# cloud-substrate.net
KiCad netlist of a schematic drawn in EAGLE
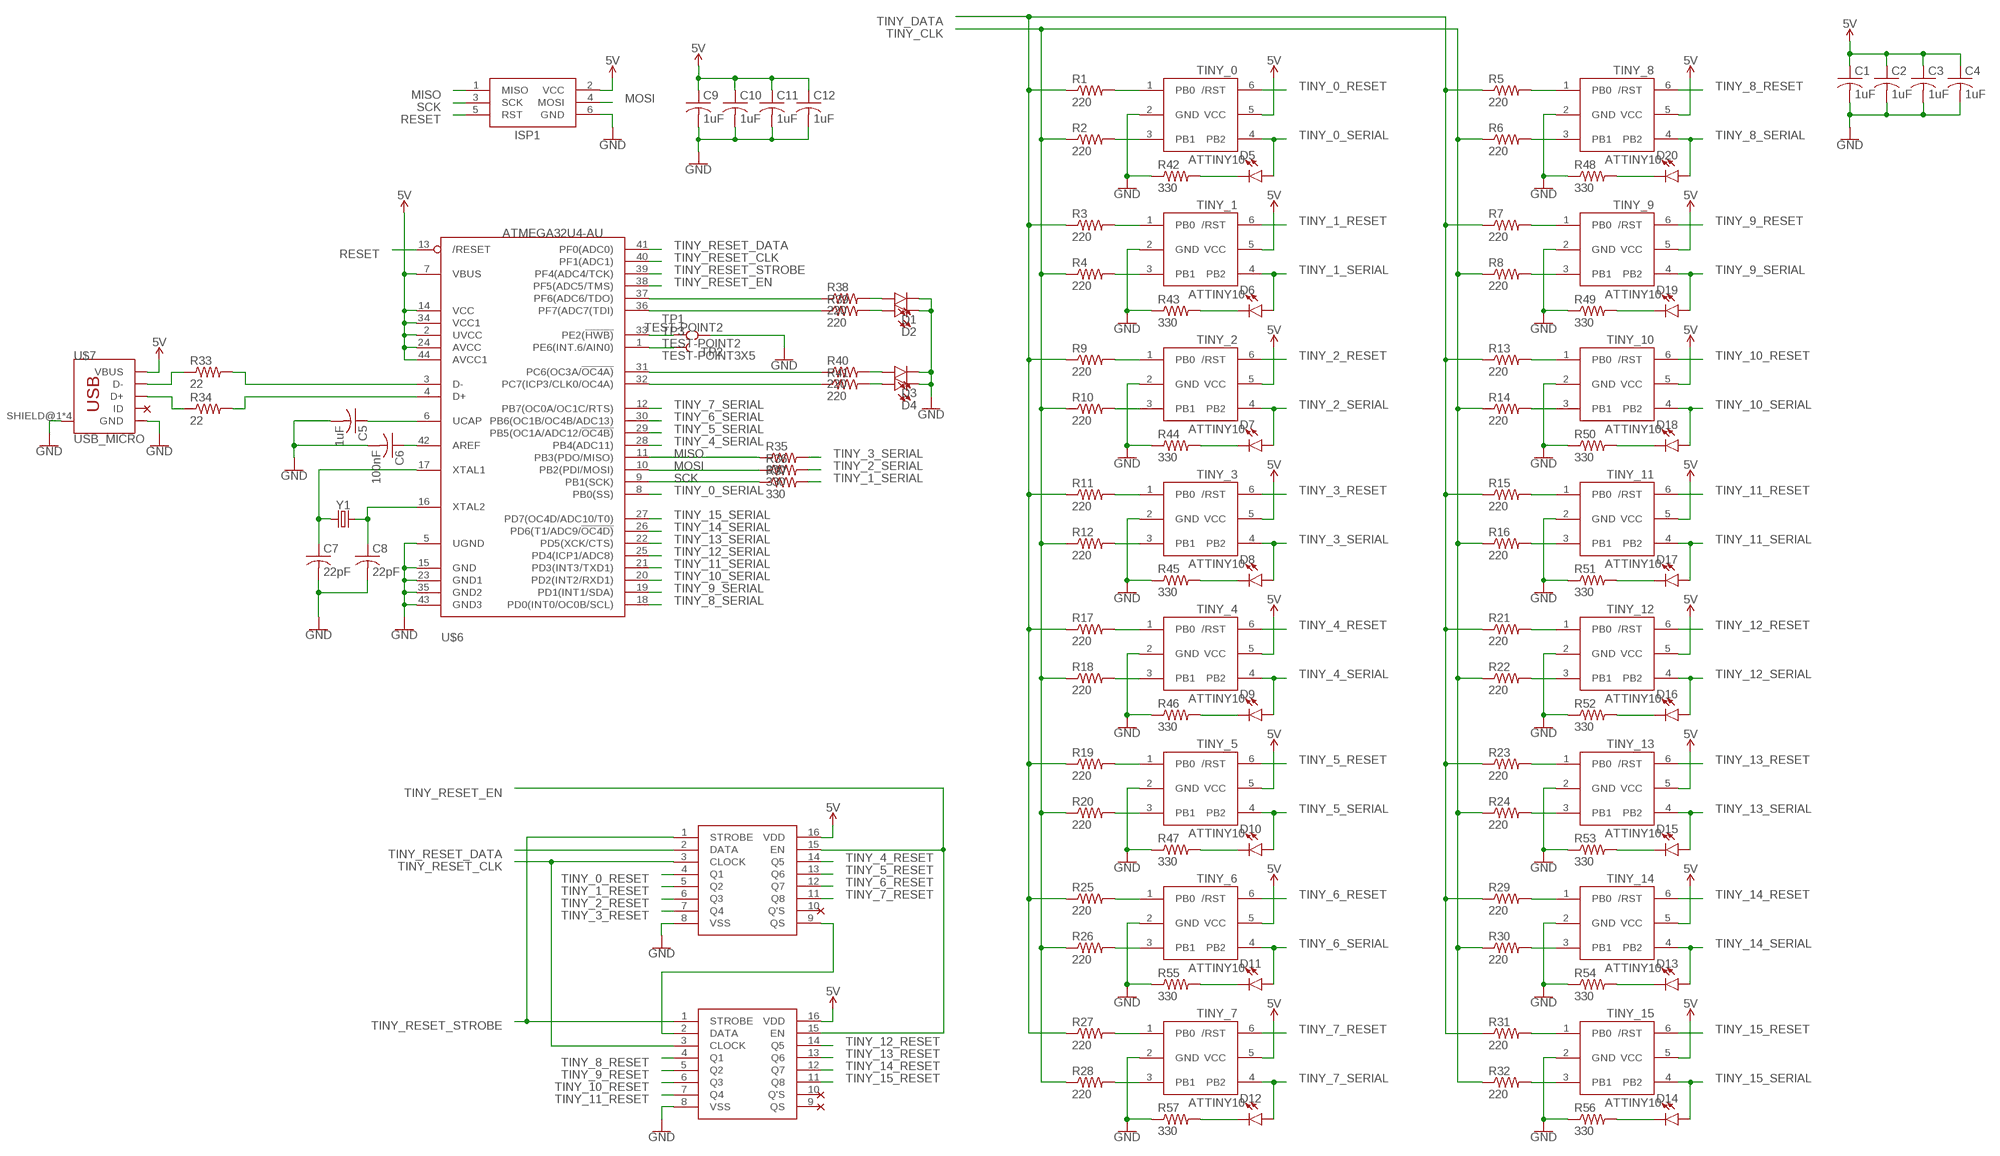
[diagram p0: schematic, sheet 1]

(export (version "E")
  (design (tool "Eeschema 10.0.6"))
  (components
    (comp (ref "C1")
      (value "1uF")
      (footprint "eagle-import:C0805")
      (libsource (lib "eagle-import") (part "C-USC0805"))
    )
    (comp (ref "C2")
      (value "1uF")
      (footprint "eagle-import:C0805")
      (libsource (lib "eagle-import") (part "C-USC0805"))
    )
    (comp (ref "C3")
      (value "1uF")
      (footprint "eagle-import:C0805")
      (libsource (lib "eagle-import") (part "C-USC0805"))
    )
    (comp (ref "C4")
      (value "1uF")
      (footprint "eagle-import:C0805")
      (libsource (lib "eagle-import") (part "C-USC0805"))
    )
    (comp (ref "C5")
      (value "1uF")
      (footprint "eagle-import:C0402")
      (libsource (lib "eagle-import") (part "C-USC0402"))
    )
    (comp (ref "C6")
      (value "100nF")
      (footprint "eagle-import:C0402")
      (libsource (lib "eagle-import") (part "C-USC0402"))
    )
    (comp (ref "C7")
      (value "22pF")
      (footprint "eagle-import:C0402")
      (libsource (lib "eagle-import") (part "C-USC0402"))
    )
    (comp (ref "C8")
      (value "22pF")
      (footprint "eagle-import:C0402")
      (libsource (lib "eagle-import") (part "C-USC0402"))
    )
    (comp (ref "C9")
      (value "1uF")
      (footprint "eagle-import:C0805")
      (libsource (lib "eagle-import") (part "C-USC0805"))
    )
    (comp (ref "C10")
      (value "1uF")
      (footprint "eagle-import:C0805")
      (libsource (lib "eagle-import") (part "C-USC0805"))
    )
    (comp (ref "C11")
      (value "1uF")
      (footprint "eagle-import:C0805")
      (libsource (lib "eagle-import") (part "C-USC0805"))
    )
    (comp (ref "C12")
      (value "1uF")
      (footprint "eagle-import:C0805")
      (libsource (lib "eagle-import") (part "C-USC0805"))
    )
    (comp (ref "D1")
      (value "LED0603")
      (footprint "eagle-import:LED-0603")
      (libsource (lib "eagle-import") (part "LED0603"))
    )
    (comp (ref "D2")
      (value "LED0603")
      (footprint "eagle-import:LED-0603")
      (libsource (lib "eagle-import") (part "LED0603"))
    )
    (comp (ref "D3")
      (value "LED0603")
      (footprint "eagle-import:LED-0603")
      (libsource (lib "eagle-import") (part "LED0603"))
    )
    (comp (ref "D4")
      (value "LED0603")
      (footprint "eagle-import:LED-0603")
      (libsource (lib "eagle-import") (part "LED0603"))
    )
    (comp (ref "D5")
      (value "LED0603")
      (footprint "eagle-import:LED-0603")
      (libsource (lib "eagle-import") (part "LED0603"))
    )
    (comp (ref "D6")
      (value "LED0603")
      (footprint "eagle-import:LED-0603")
      (libsource (lib "eagle-import") (part "LED0603"))
    )
    (comp (ref "D7")
      (value "LED0603")
      (footprint "eagle-import:LED-0603")
      (libsource (lib "eagle-import") (part "LED0603"))
    )
    (comp (ref "D8")
      (value "LED0603")
      (footprint "eagle-import:LED-0603")
      (libsource (lib "eagle-import") (part "LED0603"))
    )
    (comp (ref "D9")
      (value "LED0603")
      (footprint "eagle-import:LED-0603")
      (libsource (lib "eagle-import") (part "LED0603"))
    )
    (comp (ref "D10")
      (value "LED0603")
      (footprint "eagle-import:LED-0603")
      (libsource (lib "eagle-import") (part "LED0603"))
    )
    (comp (ref "D11")
      (value "LED0603")
      (footprint "eagle-import:LED-0603")
      (libsource (lib "eagle-import") (part "LED0603"))
    )
    (comp (ref "D12")
      (value "LED0603")
      (footprint "eagle-import:LED-0603")
      (libsource (lib "eagle-import") (part "LED0603"))
    )
    (comp (ref "D13")
      (value "LED0603")
      (footprint "eagle-import:LED-0603")
      (libsource (lib "eagle-import") (part "LED0603"))
    )
    (comp (ref "D14")
      (value "LED0603")
      (footprint "eagle-import:LED-0603")
      (libsource (lib "eagle-import") (part "LED0603"))
    )
    (comp (ref "D15")
      (value "LED0603")
      (footprint "eagle-import:LED-0603")
      (libsource (lib "eagle-import") (part "LED0603"))
    )
    (comp (ref "D16")
      (value "LED0603")
      (footprint "eagle-import:LED-0603")
      (libsource (lib "eagle-import") (part "LED0603"))
    )
    (comp (ref "D17")
      (value "LED0603")
      (footprint "eagle-import:LED-0603")
      (libsource (lib "eagle-import") (part "LED0603"))
    )
    (comp (ref "D18")
      (value "LED0603")
      (footprint "eagle-import:LED-0603")
      (libsource (lib "eagle-import") (part "LED0603"))
    )
    (comp (ref "D19")
      (value "LED0603")
      (footprint "eagle-import:LED-0603")
      (libsource (lib "eagle-import") (part "LED0603"))
    )
    (comp (ref "D20")
      (value "LED0603")
      (footprint "eagle-import:LED-0603")
      (libsource (lib "eagle-import") (part "LED0603"))
    )
    (comp (ref "ISP1")
      (value "AVRISP-6")
      (footprint "eagle-import:AVRISP")
      (libsource (lib "eagle-import") (part "AVRISP-6"))
    )
    (comp (ref "R1")
      (value "220")
      (footprint "eagle-import:R0402")
      (libsource (lib "eagle-import") (part "R-US_R0402"))
    )
    (comp (ref "R2")
      (value "220")
      (footprint "eagle-import:R0402")
      (libsource (lib "eagle-import") (part "R-US_R0402"))
    )
    (comp (ref "R3")
      (value "220")
      (footprint "eagle-import:R0402")
      (libsource (lib "eagle-import") (part "R-US_R0402"))
    )
    (comp (ref "R4")
      (value "220")
      (footprint "eagle-import:R0402")
      (libsource (lib "eagle-import") (part "R-US_R0402"))
    )
    (comp (ref "R5")
      (value "220")
      (footprint "eagle-import:R0402")
      (libsource (lib "eagle-import") (part "R-US_R0402"))
    )
    (comp (ref "R6")
      (value "220")
      (footprint "eagle-import:R0402")
      (libsource (lib "eagle-import") (part "R-US_R0402"))
    )
    (comp (ref "R7")
      (value "220")
      (footprint "eagle-import:R0402")
      (libsource (lib "eagle-import") (part "R-US_R0402"))
    )
    (comp (ref "R8")
      (value "220")
      (footprint "eagle-import:R0402")
      (libsource (lib "eagle-import") (part "R-US_R0402"))
    )
    (comp (ref "R9")
      (value "220")
      (footprint "eagle-import:R0402")
      (libsource (lib "eagle-import") (part "R-US_R0402"))
    )
    (comp (ref "R10")
      (value "220")
      (footprint "eagle-import:R0402")
      (libsource (lib "eagle-import") (part "R-US_R0402"))
    )
    (comp (ref "R11")
      (value "220")
      (footprint "eagle-import:R0402")
      (libsource (lib "eagle-import") (part "R-US_R0402"))
    )
    (comp (ref "R12")
      (value "220")
      (footprint "eagle-import:R0402")
      (libsource (lib "eagle-import") (part "R-US_R0402"))
    )
    (comp (ref "R13")
      (value "220")
      (footprint "eagle-import:R0402")
      (libsource (lib "eagle-import") (part "R-US_R0402"))
    )
    (comp (ref "R14")
      (value "220")
      (footprint "eagle-import:R0402")
      (libsource (lib "eagle-import") (part "R-US_R0402"))
    )
    (comp (ref "R15")
      (value "220")
      (footprint "eagle-import:R0402")
      (libsource (lib "eagle-import") (part "R-US_R0402"))
    )
    (comp (ref "R16")
      (value "220")
      (footprint "eagle-import:R0402")
      (libsource (lib "eagle-import") (part "R-US_R0402"))
    )
    (comp (ref "R17")
      (value "220")
      (footprint "eagle-import:R0402")
      (libsource (lib "eagle-import") (part "R-US_R0402"))
    )
    (comp (ref "R18")
      (value "220")
      (footprint "eagle-import:R0402")
      (libsource (lib "eagle-import") (part "R-US_R0402"))
    )
    (comp (ref "R19")
      (value "220")
      (footprint "eagle-import:R0402")
      (libsource (lib "eagle-import") (part "R-US_R0402"))
    )
    (comp (ref "R20")
      (value "220")
      (footprint "eagle-import:R0402")
      (libsource (lib "eagle-import") (part "R-US_R0402"))
    )
    (comp (ref "R21")
      (value "220")
      (footprint "eagle-import:R0402")
      (libsource (lib "eagle-import") (part "R-US_R0402"))
    )
    (comp (ref "R22")
      (value "220")
      (footprint "eagle-import:R0402")
      (libsource (lib "eagle-import") (part "R-US_R0402"))
    )
    (comp (ref "R23")
      (value "220")
      (footprint "eagle-import:R0402")
      (libsource (lib "eagle-import") (part "R-US_R0402"))
    )
    (comp (ref "R24")
      (value "220")
      (footprint "eagle-import:R0402")
      (libsource (lib "eagle-import") (part "R-US_R0402"))
    )
    (comp (ref "R25")
      (value "220")
      (footprint "eagle-import:R0402")
      (libsource (lib "eagle-import") (part "R-US_R0402"))
    )
    (comp (ref "R26")
      (value "220")
      (footprint "eagle-import:R0402")
      (libsource (lib "eagle-import") (part "R-US_R0402"))
    )
    (comp (ref "R27")
      (value "220")
      (footprint "eagle-import:R0402")
      (libsource (lib "eagle-import") (part "R-US_R0402"))
    )
    (comp (ref "R28")
      (value "220")
      (footprint "eagle-import:R0402")
      (libsource (lib "eagle-import") (part "R-US_R0402"))
    )
    (comp (ref "R29")
      (value "220")
      (footprint "eagle-import:R0402")
      (libsource (lib "eagle-import") (part "R-US_R0402"))
    )
    (comp (ref "R30")
      (value "220")
      (footprint "eagle-import:R0402")
      (libsource (lib "eagle-import") (part "R-US_R0402"))
    )
    (comp (ref "R31")
      (value "220")
      (footprint "eagle-import:R0402")
      (libsource (lib "eagle-import") (part "R-US_R0402"))
    )
    (comp (ref "R32")
      (value "220")
      (footprint "eagle-import:R0402")
      (libsource (lib "eagle-import") (part "R-US_R0402"))
    )
    (comp (ref "R33")
      (value "22")
      (footprint "eagle-import:R0402")
      (libsource (lib "eagle-import") (part "R-US_R0402"))
    )
    (comp (ref "R34")
      (value "22")
      (footprint "eagle-import:R0402")
      (libsource (lib "eagle-import") (part "R-US_R0402"))
    )
    (comp (ref "R35")
      (value "330")
      (footprint "eagle-import:R0402")
      (libsource (lib "eagle-import") (part "R-US_R0402"))
    )
    (comp (ref "R36")
      (value "330")
      (footprint "eagle-import:R0402")
      (libsource (lib "eagle-import") (part "R-US_R0402"))
    )
    (comp (ref "R37")
      (value "330")
      (footprint "eagle-import:R0402")
      (libsource (lib "eagle-import") (part "R-US_R0402"))
    )
    (comp (ref "R38")
      (value "220")
      (footprint "eagle-import:R0402")
      (libsource (lib "eagle-import") (part "R-US_R0402"))
    )
    (comp (ref "R39")
      (value "220")
      (footprint "eagle-import:R0402")
      (libsource (lib "eagle-import") (part "R-US_R0402"))
    )
    (comp (ref "R40")
      (value "220")
      (footprint "eagle-import:R0402")
      (libsource (lib "eagle-import") (part "R-US_R0402"))
    )
    (comp (ref "R41")
      (value "220")
      (footprint "eagle-import:R0402")
      (libsource (lib "eagle-import") (part "R-US_R0402"))
    )
    (comp (ref "R42")
      (value "330")
      (footprint "eagle-import:R0402")
      (libsource (lib "eagle-import") (part "R-US_R0402"))
    )
    (comp (ref "R43")
      (value "330")
      (footprint "eagle-import:R0402")
      (libsource (lib "eagle-import") (part "R-US_R0402"))
    )
    (comp (ref "R44")
      (value "330")
      (footprint "eagle-import:R0402")
      (libsource (lib "eagle-import") (part "R-US_R0402"))
    )
    (comp (ref "R45")
      (value "330")
      (footprint "eagle-import:R0402")
      (libsource (lib "eagle-import") (part "R-US_R0402"))
    )
    (comp (ref "R46")
      (value "330")
      (footprint "eagle-import:R0402")
      (libsource (lib "eagle-import") (part "R-US_R0402"))
    )
    (comp (ref "R47")
      (value "330")
      (footprint "eagle-import:R0402")
      (libsource (lib "eagle-import") (part "R-US_R0402"))
    )
    (comp (ref "R48")
      (value "330")
      (footprint "eagle-import:R0402")
      (libsource (lib "eagle-import") (part "R-US_R0402"))
    )
    (comp (ref "R49")
      (value "330")
      (footprint "eagle-import:R0402")
      (libsource (lib "eagle-import") (part "R-US_R0402"))
    )
    (comp (ref "R50")
      (value "330")
      (footprint "eagle-import:R0402")
      (libsource (lib "eagle-import") (part "R-US_R0402"))
    )
    (comp (ref "R51")
      (value "330")
      (footprint "eagle-import:R0402")
      (libsource (lib "eagle-import") (part "R-US_R0402"))
    )
    (comp (ref "R52")
      (value "330")
      (footprint "eagle-import:R0402")
      (libsource (lib "eagle-import") (part "R-US_R0402"))
    )
    (comp (ref "R53")
      (value "330")
      (footprint "eagle-import:R0402")
      (libsource (lib "eagle-import") (part "R-US_R0402"))
    )
    (comp (ref "R54")
      (value "330")
      (footprint "eagle-import:R0402")
      (libsource (lib "eagle-import") (part "R-US_R0402"))
    )
    (comp (ref "R55")
      (value "330")
      (footprint "eagle-import:R0402")
      (libsource (lib "eagle-import") (part "R-US_R0402"))
    )
    (comp (ref "R56")
      (value "330")
      (footprint "eagle-import:R0402")
      (libsource (lib "eagle-import") (part "R-US_R0402"))
    )
    (comp (ref "R57")
      (value "330")
      (footprint "eagle-import:R0402")
      (libsource (lib "eagle-import") (part "R-US_R0402"))
    )
    (comp (ref "TINY_0")
      (value "ATTINY10")
      (footprint "eagle-import:SOT23-6")
      (libsource (lib "eagle-import") (part "ATTINY10"))
    )
    (comp (ref "TINY_1")
      (value "ATTINY10")
      (footprint "eagle-import:SOT23-6")
      (libsource (lib "eagle-import") (part "ATTINY10"))
    )
    (comp (ref "TINY_2")
      (value "ATTINY10")
      (footprint "eagle-import:SOT23-6")
      (libsource (lib "eagle-import") (part "ATTINY10"))
    )
    (comp (ref "TINY_3")
      (value "ATTINY10")
      (footprint "eagle-import:SOT23-6")
      (libsource (lib "eagle-import") (part "ATTINY10"))
    )
    (comp (ref "TINY_4")
      (value "ATTINY10")
      (footprint "eagle-import:SOT23-6")
      (libsource (lib "eagle-import") (part "ATTINY10"))
    )
    (comp (ref "TINY_5")
      (value "ATTINY10")
      (footprint "eagle-import:SOT23-6")
      (libsource (lib "eagle-import") (part "ATTINY10"))
    )
    (comp (ref "TINY_6")
      (value "ATTINY10")
      (footprint "eagle-import:SOT23-6")
      (libsource (lib "eagle-import") (part "ATTINY10"))
    )
    (comp (ref "TINY_7")
      (value "ATTINY10")
      (footprint "eagle-import:SOT23-6")
      (libsource (lib "eagle-import") (part "ATTINY10"))
    )
    (comp (ref "TINY_8")
      (value "ATTINY10")
      (footprint "eagle-import:SOT23-6")
      (libsource (lib "eagle-import") (part "ATTINY10"))
    )
    (comp (ref "TINY_9")
      (value "ATTINY10")
      (footprint "eagle-import:SOT23-6")
      (libsource (lib "eagle-import") (part "ATTINY10"))
    )
    (comp (ref "TINY_10")
      (value "ATTINY10")
      (footprint "eagle-import:SOT23-6")
      (libsource (lib "eagle-import") (part "ATTINY10"))
    )
    (comp (ref "TINY_11")
      (value "ATTINY10")
      (footprint "eagle-import:SOT23-6")
      (libsource (lib "eagle-import") (part "ATTINY10"))
    )
    (comp (ref "TINY_12")
      (value "ATTINY10")
      (footprint "eagle-import:SOT23-6")
      (libsource (lib "eagle-import") (part "ATTINY10"))
    )
    (comp (ref "TINY_13")
      (value "ATTINY10")
      (footprint "eagle-import:SOT23-6")
      (libsource (lib "eagle-import") (part "ATTINY10"))
    )
    (comp (ref "TINY_14")
      (value "ATTINY10")
      (footprint "eagle-import:SOT23-6")
      (libsource (lib "eagle-import") (part "ATTINY10"))
    )
    (comp (ref "TINY_15")
      (value "ATTINY10")
      (footprint "eagle-import:SOT23-6")
      (libsource (lib "eagle-import") (part "ATTINY10"))
    )
    (comp (ref "TP1")
      (value "TEST-POINT2")
      (footprint "eagle-import:PAD.02X.02")
      (libsource (lib "eagle-import") (part "TEST-POINT2"))
    )
    (comp (ref "TP2")
      (value "TEST-POINT2")
      (footprint "eagle-import:PAD.02X.02")
      (libsource (lib "eagle-import") (part "TEST-POINT2"))
    )
    (comp (ref "TP3")
      (value "TEST-POINT3X5")
      (footprint "eagle-import:PAD.03X.05")
      (libsource (lib "eagle-import") (part "TEST-POINT3X5"))
    )
    (comp (ref "U$1")
      (value "CD4094B")
      (footprint "eagle-import:TSSOP16")
      (libsource (lib "eagle-import") (part "CD4094B"))
    )
    (comp (ref "U$2")
      (value "CD4094B")
      (footprint "eagle-import:TSSOP16")
      (libsource (lib "eagle-import") (part "CD4094B"))
    )
    (comp (ref "U$6")
      (value "ATMEGA32U4-AU")
      (footprint "eagle-import:TQFP44")
      (libsource (lib "eagle-import") (part "ATMEGA32U4-AU"))
    )
    (comp (ref "U$7")
      (value "USB_MICRO")
      (footprint "eagle-import:USB_FCI_10118194")
      (libsource (lib "eagle-import") (part "USB_MICRO"))
    )
    (comp (ref "Y1")
      (value "CRYSTALSMD-3.2X2.5")
      (footprint "eagle-import:CRYSTAL-SMD-3.2X2.5MM")
      (libsource (lib "eagle-import") (part "CRYSTALSMD-3.2X2.5"))
    )
  )
  (nets
    (net (code "1") (name "/MISO") (class "Default")
      (node (ref "ISP1") (pin "1") (pinfunction "MISO_1") (pintype "input"))
      (node (ref "R35") (pin "1") (pinfunction "1_1") (pintype "passive"))
      (node (ref "U$6") (pin "11") (pinfunction "PB3(PDO/MISO)_11") (pintype "bidirectional"))
    )
    (net (code "2") (name "/MOSI") (class "Default")
      (node (ref "ISP1") (pin "4") (pinfunction "MOSI_4") (pintype "output"))
      (node (ref "R36") (pin "1") (pinfunction "1_1") (pintype "passive"))
      (node (ref "U$6") (pin "10") (pinfunction "PB2(PDI/MOSI)_10") (pintype "bidirectional"))
    )
    (net (code "3") (name "/RESET") (class "Default")
      (node (ref "ISP1") (pin "5") (pinfunction "RST_5") (pintype "output"))
      (node (ref "U$6") (pin "13") (pinfunction "/RESET_13") (pintype "bidirectional"))
    )
    (net (code "4") (name "/SCK") (class "Default")
      (node (ref "ISP1") (pin "3") (pinfunction "SCK_3") (pintype "output"))
      (node (ref "R37") (pin "1") (pinfunction "1_1") (pintype "passive"))
      (node (ref "U$6") (pin "9") (pinfunction "PB1(SCK)_9") (pintype "bidirectional"))
    )
    (net (code "5") (name "/TINY_0_RESET") (class "Default")
      (node (ref "TINY_0") (pin "6") (pinfunction "/RST_6") (pintype "bidirectional"))
      (node (ref "U$1") (pin "4") (pinfunction "Q1_4") (pintype "bidirectional"))
    )
    (net (code "6") (name "/TINY_0_SERIAL") (class "Default")
      (node (ref "D5") (pin "A") (pinfunction "A_A") (pintype "passive"))
      (node (ref "TINY_0") (pin "4") (pinfunction "PB2_4") (pintype "bidirectional"))
      (node (ref "U$6") (pin "8") (pinfunction "PB0(SS)_8") (pintype "bidirectional"))
    )
    (net (code "7") (name "/TINY_1_RESET") (class "Default")
      (node (ref "TINY_1") (pin "6") (pinfunction "/RST_6") (pintype "bidirectional"))
      (node (ref "U$1") (pin "5") (pinfunction "Q2_5") (pintype "bidirectional"))
    )
    (net (code "8") (name "/TINY_1_SERIAL") (class "Default")
      (node (ref "D6") (pin "A") (pinfunction "A_A") (pintype "passive"))
      (node (ref "R37") (pin "2") (pinfunction "2_2") (pintype "passive"))
      (node (ref "TINY_1") (pin "4") (pinfunction "PB2_4") (pintype "bidirectional"))
    )
    (net (code "9") (name "/TINY_2_RESET") (class "Default")
      (node (ref "TINY_2") (pin "6") (pinfunction "/RST_6") (pintype "bidirectional"))
      (node (ref "U$1") (pin "6") (pinfunction "Q3_6") (pintype "bidirectional"))
    )
    (net (code "10") (name "/TINY_2_SERIAL") (class "Default")
      (node (ref "D7") (pin "A") (pinfunction "A_A") (pintype "passive"))
      (node (ref "R36") (pin "2") (pinfunction "2_2") (pintype "passive"))
      (node (ref "TINY_2") (pin "4") (pinfunction "PB2_4") (pintype "bidirectional"))
    )
    (net (code "11") (name "/TINY_3_RESET") (class "Default")
      (node (ref "TINY_3") (pin "6") (pinfunction "/RST_6") (pintype "bidirectional"))
      (node (ref "U$1") (pin "7") (pinfunction "Q4_7") (pintype "bidirectional"))
    )
    (net (code "12") (name "/TINY_3_SERIAL") (class "Default")
      (node (ref "D8") (pin "A") (pinfunction "A_A") (pintype "passive"))
      (node (ref "R35") (pin "2") (pinfunction "2_2") (pintype "passive"))
      (node (ref "TINY_3") (pin "4") (pinfunction "PB2_4") (pintype "bidirectional"))
    )
    (net (code "13") (name "/TINY_4_RESET") (class "Default")
      (node (ref "TINY_4") (pin "6") (pinfunction "/RST_6") (pintype "bidirectional"))
      (node (ref "U$1") (pin "14") (pinfunction "Q5_14") (pintype "bidirectional"))
    )
    (net (code "14") (name "/TINY_4_SERIAL") (class "Default")
      (node (ref "D9") (pin "A") (pinfunction "A_A") (pintype "passive"))
      (node (ref "TINY_4") (pin "4") (pinfunction "PB2_4") (pintype "bidirectional"))
      (node (ref "U$6") (pin "28") (pinfunction "PB4(ADC11)_28") (pintype "bidirectional"))
    )
    (net (code "15") (name "/TINY_5_RESET") (class "Default")
      (node (ref "TINY_5") (pin "6") (pinfunction "/RST_6") (pintype "bidirectional"))
      (node (ref "U$1") (pin "13") (pinfunction "Q6_13") (pintype "bidirectional"))
    )
    (net (code "16") (name "/TINY_5_SERIAL") (class "Default")
      (node (ref "D10") (pin "A") (pinfunction "A_A") (pintype "passive"))
      (node (ref "TINY_5") (pin "4") (pinfunction "PB2_4") (pintype "bidirectional"))
      (node (ref "U$6") (pin "29") (pinfunction "PB5(OC1A/ADC12/~{OC4B})_29") (pintype "bidirectional"))
    )
    (net (code "17") (name "/TINY_6_RESET") (class "Default")
      (node (ref "TINY_6") (pin "6") (pinfunction "/RST_6") (pintype "bidirectional"))
      (node (ref "U$1") (pin "12") (pinfunction "Q7_12") (pintype "bidirectional"))
    )
    (net (code "18") (name "/TINY_6_SERIAL") (class "Default")
      (node (ref "D11") (pin "A") (pinfunction "A_A") (pintype "passive"))
      (node (ref "TINY_6") (pin "4") (pinfunction "PB2_4") (pintype "bidirectional"))
      (node (ref "U$6") (pin "30") (pinfunction "PB6(OC1B/OC4B/ADC13)_30") (pintype "bidirectional"))
    )
    (net (code "19") (name "/TINY_7_RESET") (class "Default")
      (node (ref "TINY_7") (pin "6") (pinfunction "/RST_6") (pintype "bidirectional"))
      (node (ref "U$1") (pin "11") (pinfunction "Q8_11") (pintype "bidirectional"))
    )
    (net (code "20") (name "/TINY_7_SERIAL") (class "Default")
      (node (ref "D12") (pin "A") (pinfunction "A_A") (pintype "passive"))
      (node (ref "TINY_7") (pin "4") (pinfunction "PB2_4") (pintype "bidirectional"))
      (node (ref "U$6") (pin "12") (pinfunction "PB7(OC0A/OC1C/RTS)_12") (pintype "bidirectional"))
    )
    (net (code "21") (name "/TINY_8_RESET") (class "Default")
      (node (ref "TINY_8") (pin "6") (pinfunction "/RST_6") (pintype "bidirectional"))
      (node (ref "U$2") (pin "4") (pinfunction "Q1_4") (pintype "bidirectional"))
    )
    (net (code "22") (name "/TINY_8_SERIAL") (class "Default")
      (node (ref "D20") (pin "A") (pinfunction "A_A") (pintype "passive"))
      (node (ref "TINY_8") (pin "4") (pinfunction "PB2_4") (pintype "bidirectional"))
      (node (ref "U$6") (pin "18") (pinfunction "PD0(INT0/OC0B/SCL)_18") (pintype "bidirectional"))
    )
    (net (code "23") (name "/TINY_9_RESET") (class "Default")
      (node (ref "TINY_9") (pin "6") (pinfunction "/RST_6") (pintype "bidirectional"))
      (node (ref "U$2") (pin "5") (pinfunction "Q2_5") (pintype "bidirectional"))
    )
    (net (code "24") (name "/TINY_9_SERIAL") (class "Default")
      (node (ref "D19") (pin "A") (pinfunction "A_A") (pintype "passive"))
      (node (ref "TINY_9") (pin "4") (pinfunction "PB2_4") (pintype "bidirectional"))
      (node (ref "U$6") (pin "19") (pinfunction "PD1(INT1/SDA)_19") (pintype "bidirectional"))
    )
    (net (code "25") (name "/TINY_10_RESET") (class "Default")
      (node (ref "TINY_10") (pin "6") (pinfunction "/RST_6") (pintype "bidirectional"))
      (node (ref "U$2") (pin "6") (pinfunction "Q3_6") (pintype "bidirectional"))
    )
    (net (code "26") (name "/TINY_10_SERIAL") (class "Default")
      (node (ref "D18") (pin "A") (pinfunction "A_A") (pintype "passive"))
      (node (ref "TINY_10") (pin "4") (pinfunction "PB2_4") (pintype "bidirectional"))
      (node (ref "U$6") (pin "20") (pinfunction "PD2(INT2/RXD1)_20") (pintype "bidirectional"))
    )
    (net (code "27") (name "/TINY_11_RESET") (class "Default")
      (node (ref "TINY_11") (pin "6") (pinfunction "/RST_6") (pintype "bidirectional"))
      (node (ref "U$2") (pin "7") (pinfunction "Q4_7") (pintype "bidirectional"))
    )
    (net (code "28") (name "/TINY_11_SERIAL") (class "Default")
      (node (ref "D17") (pin "A") (pinfunction "A_A") (pintype "passive"))
      (node (ref "TINY_11") (pin "4") (pinfunction "PB2_4") (pintype "bidirectional"))
      (node (ref "U$6") (pin "21") (pinfunction "PD3(INT3/TXD1)_21") (pintype "bidirectional"))
    )
    (net (code "29") (name "/TINY_12_RESET") (class "Default")
      (node (ref "TINY_12") (pin "6") (pinfunction "/RST_6") (pintype "bidirectional"))
      (node (ref "U$2") (pin "14") (pinfunction "Q5_14") (pintype "bidirectional"))
    )
    (net (code "30") (name "/TINY_12_SERIAL") (class "Default")
      (node (ref "D16") (pin "A") (pinfunction "A_A") (pintype "passive"))
      (node (ref "TINY_12") (pin "4") (pinfunction "PB2_4") (pintype "bidirectional"))
      (node (ref "U$6") (pin "25") (pinfunction "PD4(ICP1/ADC8)_25") (pintype "bidirectional"))
    )
    (net (code "31") (name "/TINY_13_RESET") (class "Default")
      (node (ref "TINY_13") (pin "6") (pinfunction "/RST_6") (pintype "bidirectional"))
      (node (ref "U$2") (pin "13") (pinfunction "Q6_13") (pintype "bidirectional"))
    )
    (net (code "32") (name "/TINY_13_SERIAL") (class "Default")
      (node (ref "D15") (pin "A") (pinfunction "A_A") (pintype "passive"))
      (node (ref "TINY_13") (pin "4") (pinfunction "PB2_4") (pintype "bidirectional"))
      (node (ref "U$6") (pin "22") (pinfunction "PD5(XCK/CTS)_22") (pintype "bidirectional"))
    )
    (net (code "33") (name "/TINY_14_RESET") (class "Default")
      (node (ref "TINY_14") (pin "6") (pinfunction "/RST_6") (pintype "bidirectional"))
      (node (ref "U$2") (pin "12") (pinfunction "Q7_12") (pintype "bidirectional"))
    )
    (net (code "34") (name "/TINY_14_SERIAL") (class "Default")
      (node (ref "D13") (pin "A") (pinfunction "A_A") (pintype "passive"))
      (node (ref "TINY_14") (pin "4") (pinfunction "PB2_4") (pintype "bidirectional"))
      (node (ref "U$6") (pin "26") (pinfunction "PD6(T1/ADC9/~{OC4D})_26") (pintype "bidirectional"))
    )
    (net (code "35") (name "/TINY_15_RESET") (class "Default")
      (node (ref "TINY_15") (pin "6") (pinfunction "/RST_6") (pintype "bidirectional"))
      (node (ref "U$2") (pin "11") (pinfunction "Q8_11") (pintype "bidirectional"))
    )
    (net (code "36") (name "/TINY_15_SERIAL") (class "Default")
      (node (ref "D14") (pin "A") (pinfunction "A_A") (pintype "passive"))
      (node (ref "TINY_15") (pin "4") (pinfunction "PB2_4") (pintype "bidirectional"))
      (node (ref "U$6") (pin "27") (pinfunction "PD7(OC4D/ADC10/T0)_27") (pintype "bidirectional"))
    )
    (net (code "37") (name "/TINY_CLK") (class "Default")
      (node (ref "R10") (pin "1") (pinfunction "1_1") (pintype "passive"))
      (node (ref "R12") (pin "1") (pinfunction "1_1") (pintype "passive"))
      (node (ref "R14") (pin "1") (pinfunction "1_1") (pintype "passive"))
      (node (ref "R16") (pin "1") (pinfunction "1_1") (pintype "passive"))
      (node (ref "R18") (pin "1") (pinfunction "1_1") (pintype "passive"))
      (node (ref "R2") (pin "1") (pinfunction "1_1") (pintype "passive"))
      (node (ref "R20") (pin "1") (pinfunction "1_1") (pintype "passive"))
      (node (ref "R22") (pin "1") (pinfunction "1_1") (pintype "passive"))
      (node (ref "R24") (pin "1") (pinfunction "1_1") (pintype "passive"))
      (node (ref "R26") (pin "1") (pinfunction "1_1") (pintype "passive"))
      (node (ref "R28") (pin "1") (pinfunction "1_1") (pintype "passive"))
      (node (ref "R30") (pin "1") (pinfunction "1_1") (pintype "passive"))
      (node (ref "R32") (pin "1") (pinfunction "1_1") (pintype "passive"))
      (node (ref "R4") (pin "1") (pinfunction "1_1") (pintype "passive"))
      (node (ref "R6") (pin "1") (pinfunction "1_1") (pintype "passive"))
      (node (ref "R8") (pin "1") (pinfunction "1_1") (pintype "passive"))
    )
    (net (code "38") (name "/TINY_DATA") (class "Default")
      (node (ref "R1") (pin "1") (pinfunction "1_1") (pintype "passive"))
      (node (ref "R11") (pin "1") (pinfunction "1_1") (pintype "passive"))
      (node (ref "R13") (pin "1") (pinfunction "1_1") (pintype "passive"))
      (node (ref "R15") (pin "1") (pinfunction "1_1") (pintype "passive"))
      (node (ref "R17") (pin "1") (pinfunction "1_1") (pintype "passive"))
      (node (ref "R19") (pin "1") (pinfunction "1_1") (pintype "passive"))
      (node (ref "R21") (pin "1") (pinfunction "1_1") (pintype "passive"))
      (node (ref "R23") (pin "1") (pinfunction "1_1") (pintype "passive"))
      (node (ref "R25") (pin "1") (pinfunction "1_1") (pintype "passive"))
      (node (ref "R27") (pin "1") (pinfunction "1_1") (pintype "passive"))
      (node (ref "R29") (pin "1") (pinfunction "1_1") (pintype "passive"))
      (node (ref "R3") (pin "1") (pinfunction "1_1") (pintype "passive"))
      (node (ref "R31") (pin "1") (pinfunction "1_1") (pintype "passive"))
      (node (ref "R5") (pin "1") (pinfunction "1_1") (pintype "passive"))
      (node (ref "R7") (pin "1") (pinfunction "1_1") (pintype "passive"))
      (node (ref "R9") (pin "1") (pinfunction "1_1") (pintype "passive"))
    )
    (net (code "39") (name "/TINY_RESET_CLK") (class "Default")
      (node (ref "U$1") (pin "3") (pinfunction "CLOCK_3") (pintype "bidirectional"))
      (node (ref "U$2") (pin "3") (pinfunction "CLOCK_3") (pintype "bidirectional"))
      (node (ref "U$6") (pin "40") (pinfunction "PF1(ADC1)_40") (pintype "bidirectional"))
    )
    (net (code "40") (name "/TINY_RESET_DATA") (class "Default")
      (node (ref "U$1") (pin "2") (pinfunction "DATA_2") (pintype "bidirectional"))
      (node (ref "U$6") (pin "41") (pinfunction "PF0(ADC0)_41") (pintype "bidirectional"))
    )
    (net (code "41") (name "/TINY_RESET_EN") (class "Default")
      (node (ref "U$1") (pin "15") (pinfunction "EN_15") (pintype "bidirectional"))
      (node (ref "U$2") (pin "15") (pinfunction "EN_15") (pintype "bidirectional"))
      (node (ref "U$6") (pin "38") (pinfunction "PF5(ADC5/TMS)_38") (pintype "bidirectional"))
    )
    (net (code "42") (name "/TINY_RESET_STROBE") (class "Default")
      (node (ref "U$1") (pin "1") (pinfunction "STROBE_1") (pintype "bidirectional"))
      (node (ref "U$2") (pin "1") (pinfunction "STROBE_1") (pintype "bidirectional"))
      (node (ref "U$6") (pin "39") (pinfunction "PF4(ADC4/TCK)_39") (pintype "bidirectional"))
    )
    (net (code "43") (name "5V") (class "Default")
      (node (ref "C1") (pin "1") (pinfunction "1_1") (pintype "passive"))
      (node (ref "C10") (pin "1") (pinfunction "1_1") (pintype "passive"))
      (node (ref "C11") (pin "1") (pinfunction "1_1") (pintype "passive"))
      (node (ref "C12") (pin "1") (pinfunction "1_1") (pintype "passive"))
      (node (ref "C2") (pin "1") (pinfunction "1_1") (pintype "passive"))
      (node (ref "C3") (pin "1") (pinfunction "1_1") (pintype "passive"))
      (node (ref "C4") (pin "1") (pinfunction "1_1") (pintype "passive"))
      (node (ref "C9") (pin "1") (pinfunction "1_1") (pintype "passive"))
      (node (ref "ISP1") (pin "2") (pinfunction "VCC_2") (pintype "power_in"))
      (node (ref "TINY_0") (pin "5") (pinfunction "VCC_5") (pintype "power_in"))
      (node (ref "TINY_1") (pin "5") (pinfunction "VCC_5") (pintype "power_in"))
      (node (ref "TINY_10") (pin "5") (pinfunction "VCC_5") (pintype "power_in"))
      (node (ref "TINY_11") (pin "5") (pinfunction "VCC_5") (pintype "power_in"))
      (node (ref "TINY_12") (pin "5") (pinfunction "VCC_5") (pintype "power_in"))
      (node (ref "TINY_13") (pin "5") (pinfunction "VCC_5") (pintype "power_in"))
      (node (ref "TINY_14") (pin "5") (pinfunction "VCC_5") (pintype "power_in"))
      (node (ref "TINY_15") (pin "5") (pinfunction "VCC_5") (pintype "power_in"))
      (node (ref "TINY_2") (pin "5") (pinfunction "VCC_5") (pintype "power_in"))
      (node (ref "TINY_3") (pin "5") (pinfunction "VCC_5") (pintype "power_in"))
      (node (ref "TINY_4") (pin "5") (pinfunction "VCC_5") (pintype "power_in"))
      (node (ref "TINY_5") (pin "5") (pinfunction "VCC_5") (pintype "power_in"))
      (node (ref "TINY_6") (pin "5") (pinfunction "VCC_5") (pintype "power_in"))
      (node (ref "TINY_7") (pin "5") (pinfunction "VCC_5") (pintype "power_in"))
      (node (ref "TINY_8") (pin "5") (pinfunction "VCC_5") (pintype "power_in"))
      (node (ref "TINY_9") (pin "5") (pinfunction "VCC_5") (pintype "power_in"))
      (node (ref "U$1") (pin "16") (pinfunction "VDD_16") (pintype "bidirectional"))
      (node (ref "U$2") (pin "16") (pinfunction "VDD_16") (pintype "bidirectional"))
      (node (ref "U$6") (pin "14") (pinfunction "VCC_14") (pintype "bidirectional"))
      (node (ref "U$6") (pin "2") (pinfunction "UVCC_2") (pintype "bidirectional"))
      (node (ref "U$6") (pin "24") (pinfunction "AVCC_24") (pintype "bidirectional"))
      (node (ref "U$6") (pin "34") (pinfunction "VCC1_34") (pintype "bidirectional"))
      (node (ref "U$6") (pin "44") (pinfunction "AVCC1_44") (pintype "bidirectional"))
      (node (ref "U$6") (pin "7") (pinfunction "VBUS_7") (pintype "bidirectional"))
      (node (ref "U$7") (pin "1") (pinfunction "VBUS_1") (pintype "power_in"))
    )
    (net (code "44") (name "GND") (class "Default")
      (node (ref "C1") (pin "2") (pinfunction "2_2") (pintype "passive"))
      (node (ref "C10") (pin "2") (pinfunction "2_2") (pintype "passive"))
      (node (ref "C11") (pin "2") (pinfunction "2_2") (pintype "passive"))
      (node (ref "C12") (pin "2") (pinfunction "2_2") (pintype "passive"))
      (node (ref "C2") (pin "2") (pinfunction "2_2") (pintype "passive"))
      (node (ref "C3") (pin "2") (pinfunction "2_2") (pintype "passive"))
      (node (ref "C4") (pin "2") (pinfunction "2_2") (pintype "passive"))
      (node (ref "C5") (pin "2") (pinfunction "2_2") (pintype "passive"))
      (node (ref "C6") (pin "2") (pinfunction "2_2") (pintype "passive"))
      (node (ref "C7") (pin "2") (pinfunction "2_2") (pintype "passive"))
      (node (ref "C8") (pin "2") (pinfunction "2_2") (pintype "passive"))
      (node (ref "C9") (pin "2") (pinfunction "2_2") (pintype "passive"))
      (node (ref "D1") (pin "C") (pinfunction "C_C") (pintype "passive"))
      (node (ref "D2") (pin "C") (pinfunction "C_C") (pintype "passive"))
      (node (ref "D3") (pin "C") (pinfunction "C_C") (pintype "passive"))
      (node (ref "D4") (pin "C") (pinfunction "C_C") (pintype "passive"))
      (node (ref "ISP1") (pin "6") (pinfunction "GND_6") (pintype "power_in"))
      (node (ref "R42") (pin "1") (pinfunction "1_1") (pintype "passive"))
      (node (ref "R43") (pin "1") (pinfunction "1_1") (pintype "passive"))
      (node (ref "R44") (pin "1") (pinfunction "1_1") (pintype "passive"))
      (node (ref "R45") (pin "1") (pinfunction "1_1") (pintype "passive"))
      (node (ref "R46") (pin "1") (pinfunction "1_1") (pintype "passive"))
      (node (ref "R47") (pin "1") (pinfunction "1_1") (pintype "passive"))
      (node (ref "R48") (pin "1") (pinfunction "1_1") (pintype "passive"))
      (node (ref "R49") (pin "1") (pinfunction "1_1") (pintype "passive"))
      (node (ref "R50") (pin "1") (pinfunction "1_1") (pintype "passive"))
      (node (ref "R51") (pin "1") (pinfunction "1_1") (pintype "passive"))
      (node (ref "R52") (pin "1") (pinfunction "1_1") (pintype "passive"))
      (node (ref "R53") (pin "1") (pinfunction "1_1") (pintype "passive"))
      (node (ref "R54") (pin "1") (pinfunction "1_1") (pintype "passive"))
      (node (ref "R55") (pin "1") (pinfunction "1_1") (pintype "passive"))
      (node (ref "R56") (pin "1") (pinfunction "1_1") (pintype "passive"))
      (node (ref "R57") (pin "1") (pinfunction "1_1") (pintype "passive"))
      (node (ref "TINY_0") (pin "2") (pinfunction "GND_2") (pintype "power_in"))
      (node (ref "TINY_1") (pin "2") (pinfunction "GND_2") (pintype "power_in"))
      (node (ref "TINY_10") (pin "2") (pinfunction "GND_2") (pintype "power_in"))
      (node (ref "TINY_11") (pin "2") (pinfunction "GND_2") (pintype "power_in"))
      (node (ref "TINY_12") (pin "2") (pinfunction "GND_2") (pintype "power_in"))
      (node (ref "TINY_13") (pin "2") (pinfunction "GND_2") (pintype "power_in"))
      (node (ref "TINY_14") (pin "2") (pinfunction "GND_2") (pintype "power_in"))
      (node (ref "TINY_15") (pin "2") (pinfunction "GND_2") (pintype "power_in"))
      (node (ref "TINY_2") (pin "2") (pinfunction "GND_2") (pintype "power_in"))
      (node (ref "TINY_3") (pin "2") (pinfunction "GND_2") (pintype "power_in"))
      (node (ref "TINY_4") (pin "2") (pinfunction "GND_2") (pintype "power_in"))
      (node (ref "TINY_5") (pin "2") (pinfunction "GND_2") (pintype "power_in"))
      (node (ref "TINY_6") (pin "2") (pinfunction "GND_2") (pintype "power_in"))
      (node (ref "TINY_7") (pin "2") (pinfunction "GND_2") (pintype "power_in"))
      (node (ref "TINY_8") (pin "2") (pinfunction "GND_2") (pintype "power_in"))
      (node (ref "TINY_9") (pin "2") (pinfunction "GND_2") (pintype "power_in"))
      (node (ref "TP2") (pin "P$1") (pinfunction "1_P$1") (pintype "bidirectional"))
      (node (ref "U$1") (pin "8") (pinfunction "VSS_8") (pintype "bidirectional"))
      (node (ref "U$2") (pin "8") (pinfunction "VSS_8") (pintype "bidirectional"))
      (node (ref "U$6") (pin "15") (pinfunction "GND_15") (pintype "bidirectional"))
      (node (ref "U$6") (pin "23") (pinfunction "GND1_23") (pintype "bidirectional"))
      (node (ref "U$6") (pin "35") (pinfunction "GND2_35") (pintype "bidirectional"))
      (node (ref "U$6") (pin "43") (pinfunction "GND3_43") (pintype "bidirectional"))
      (node (ref "U$6") (pin "5") (pinfunction "UGND_5") (pintype "bidirectional"))
      (node (ref "U$7") (pin "5") (pinfunction "GND_5") (pintype "power_in"))
      (node (ref "U$7") (pin "SHIELD@1") (pinfunction "SHIELD_SHIELD@1") (pintype "bidirectional"))
      (node (ref "U$7") (pin "SHIELD@2") (pinfunction "SHIELD_SHIELD@2") (pintype "bidirectional"))
      (node (ref "U$7") (pin "SHIELD@3") (pinfunction "SHIELD_SHIELD@3") (pintype "bidirectional"))
      (node (ref "U$7") (pin "SHIELD@4") (pinfunction "SHIELD_SHIELD@4") (pintype "bidirectional"))
    )
    (net (code "45") (name "Net-(D1-PadA)") (class "Default")
      (node (ref "D1") (pin "A") (pinfunction "A_A") (pintype "passive"))
      (node (ref "R38") (pin "2") (pinfunction "2_2") (pintype "passive"))
    )
    (net (code "46") (name "Net-(D2-PadA)") (class "Default")
      (node (ref "D2") (pin "A") (pinfunction "A_A") (pintype "passive"))
      (node (ref "R39") (pin "2") (pinfunction "2_2") (pintype "passive"))
    )
    (net (code "47") (name "Net-(D3-PadA)") (class "Default")
      (node (ref "D3") (pin "A") (pinfunction "A_A") (pintype "passive"))
      (node (ref "R40") (pin "2") (pinfunction "2_2") (pintype "passive"))
    )
    (net (code "48") (name "Net-(D4-PadA)") (class "Default")
      (node (ref "D4") (pin "A") (pinfunction "A_A") (pintype "passive"))
      (node (ref "R41") (pin "2") (pinfunction "2_2") (pintype "passive"))
    )
    (net (code "49") (name "Net-(D5-PadC)") (class "Default")
      (node (ref "D5") (pin "C") (pinfunction "C_C") (pintype "passive"))
      (node (ref "R42") (pin "2") (pinfunction "2_2") (pintype "passive"))
    )
    (net (code "50") (name "Net-(D6-PadC)") (class "Default")
      (node (ref "D6") (pin "C") (pinfunction "C_C") (pintype "passive"))
      (node (ref "R43") (pin "2") (pinfunction "2_2") (pintype "passive"))
    )
    (net (code "51") (name "Net-(D7-PadC)") (class "Default")
      (node (ref "D7") (pin "C") (pinfunction "C_C") (pintype "passive"))
      (node (ref "R44") (pin "2") (pinfunction "2_2") (pintype "passive"))
    )
    (net (code "52") (name "Net-(D8-PadC)") (class "Default")
      (node (ref "D8") (pin "C") (pinfunction "C_C") (pintype "passive"))
      (node (ref "R45") (pin "2") (pinfunction "2_2") (pintype "passive"))
    )
    (net (code "53") (name "Net-(D9-PadC)") (class "Default")
      (node (ref "D9") (pin "C") (pinfunction "C_C") (pintype "passive"))
      (node (ref "R46") (pin "2") (pinfunction "2_2") (pintype "passive"))
    )
    (net (code "54") (name "Net-(D10-PadC)") (class "Default")
      (node (ref "D10") (pin "C") (pinfunction "C_C") (pintype "passive"))
      (node (ref "R47") (pin "2") (pinfunction "2_2") (pintype "passive"))
    )
    (net (code "55") (name "Net-(D11-PadC)") (class "Default")
      (node (ref "D11") (pin "C") (pinfunction "C_C") (pintype "passive"))
      (node (ref "R55") (pin "2") (pinfunction "2_2") (pintype "passive"))
    )
    (net (code "56") (name "Net-(D12-PadC)") (class "Default")
      (node (ref "D12") (pin "C") (pinfunction "C_C") (pintype "passive"))
      (node (ref "R57") (pin "2") (pinfunction "2_2") (pintype "passive"))
    )
    (net (code "57") (name "Net-(D13-PadC)") (class "Default")
      (node (ref "D13") (pin "C") (pinfunction "C_C") (pintype "passive"))
      (node (ref "R54") (pin "2") (pinfunction "2_2") (pintype "passive"))
    )
    (net (code "58") (name "Net-(D14-PadC)") (class "Default")
      (node (ref "D14") (pin "C") (pinfunction "C_C") (pintype "passive"))
      (node (ref "R56") (pin "2") (pinfunction "2_2") (pintype "passive"))
    )
    (net (code "59") (name "Net-(D15-PadC)") (class "Default")
      (node (ref "D15") (pin "C") (pinfunction "C_C") (pintype "passive"))
      (node (ref "R53") (pin "2") (pinfunction "2_2") (pintype "passive"))
    )
    (net (code "60") (name "Net-(D16-PadC)") (class "Default")
      (node (ref "D16") (pin "C") (pinfunction "C_C") (pintype "passive"))
      (node (ref "R52") (pin "2") (pinfunction "2_2") (pintype "passive"))
    )
    (net (code "61") (name "Net-(D17-PadC)") (class "Default")
      (node (ref "D17") (pin "C") (pinfunction "C_C") (pintype "passive"))
      (node (ref "R51") (pin "2") (pinfunction "2_2") (pintype "passive"))
    )
    (net (code "62") (name "Net-(D18-PadC)") (class "Default")
      (node (ref "D18") (pin "C") (pinfunction "C_C") (pintype "passive"))
      (node (ref "R50") (pin "2") (pinfunction "2_2") (pintype "passive"))
    )
    (net (code "63") (name "Net-(D19-PadC)") (class "Default")
      (node (ref "D19") (pin "C") (pinfunction "C_C") (pintype "passive"))
      (node (ref "R49") (pin "2") (pinfunction "2_2") (pintype "passive"))
    )
    (net (code "64") (name "Net-(D20-PadC)") (class "Default")
      (node (ref "D20") (pin "C") (pinfunction "C_C") (pintype "passive"))
      (node (ref "R48") (pin "2") (pinfunction "2_2") (pintype "passive"))
    )
    (net (code "65") (name "Net-(TINY_0-PB0)") (class "Default")
      (node (ref "R1") (pin "2") (pinfunction "2_2") (pintype "passive"))
      (node (ref "TINY_0") (pin "1") (pinfunction "PB0_1") (pintype "bidirectional"))
    )
    (net (code "66") (name "Net-(TINY_0-PB1)") (class "Default")
      (node (ref "R2") (pin "2") (pinfunction "2_2") (pintype "passive"))
      (node (ref "TINY_0") (pin "3") (pinfunction "PB1_3") (pintype "bidirectional"))
    )
    (net (code "67") (name "Net-(TINY_1-PB0)") (class "Default")
      (node (ref "R3") (pin "2") (pinfunction "2_2") (pintype "passive"))
      (node (ref "TINY_1") (pin "1") (pinfunction "PB0_1") (pintype "bidirectional"))
    )
    (net (code "68") (name "Net-(TINY_1-PB1)") (class "Default")
      (node (ref "R4") (pin "2") (pinfunction "2_2") (pintype "passive"))
      (node (ref "TINY_1") (pin "3") (pinfunction "PB1_3") (pintype "bidirectional"))
    )
    (net (code "69") (name "Net-(TINY_2-PB0)") (class "Default")
      (node (ref "R9") (pin "2") (pinfunction "2_2") (pintype "passive"))
      (node (ref "TINY_2") (pin "1") (pinfunction "PB0_1") (pintype "bidirectional"))
    )
    (net (code "70") (name "Net-(TINY_2-PB1)") (class "Default")
      (node (ref "R10") (pin "2") (pinfunction "2_2") (pintype "passive"))
      (node (ref "TINY_2") (pin "3") (pinfunction "PB1_3") (pintype "bidirectional"))
    )
    (net (code "71") (name "Net-(TINY_3-PB0)") (class "Default")
      (node (ref "R11") (pin "2") (pinfunction "2_2") (pintype "passive"))
      (node (ref "TINY_3") (pin "1") (pinfunction "PB0_1") (pintype "bidirectional"))
    )
    (net (code "72") (name "Net-(TINY_3-PB1)") (class "Default")
      (node (ref "R12") (pin "2") (pinfunction "2_2") (pintype "passive"))
      (node (ref "TINY_3") (pin "3") (pinfunction "PB1_3") (pintype "bidirectional"))
    )
    (net (code "73") (name "Net-(TINY_4-PB0)") (class "Default")
      (node (ref "R17") (pin "2") (pinfunction "2_2") (pintype "passive"))
      (node (ref "TINY_4") (pin "1") (pinfunction "PB0_1") (pintype "bidirectional"))
    )
    (net (code "74") (name "Net-(TINY_4-PB1)") (class "Default")
      (node (ref "R18") (pin "2") (pinfunction "2_2") (pintype "passive"))
      (node (ref "TINY_4") (pin "3") (pinfunction "PB1_3") (pintype "bidirectional"))
    )
    (net (code "75") (name "Net-(TINY_5-PB0)") (class "Default")
      (node (ref "R19") (pin "2") (pinfunction "2_2") (pintype "passive"))
      (node (ref "TINY_5") (pin "1") (pinfunction "PB0_1") (pintype "bidirectional"))
    )
    (net (code "76") (name "Net-(TINY_5-PB1)") (class "Default")
      (node (ref "R20") (pin "2") (pinfunction "2_2") (pintype "passive"))
      (node (ref "TINY_5") (pin "3") (pinfunction "PB1_3") (pintype "bidirectional"))
    )
    (net (code "77") (name "Net-(TINY_6-PB0)") (class "Default")
      (node (ref "R25") (pin "2") (pinfunction "2_2") (pintype "passive"))
      (node (ref "TINY_6") (pin "1") (pinfunction "PB0_1") (pintype "bidirectional"))
    )
    (net (code "78") (name "Net-(TINY_6-PB1)") (class "Default")
      (node (ref "R26") (pin "2") (pinfunction "2_2") (pintype "passive"))
      (node (ref "TINY_6") (pin "3") (pinfunction "PB1_3") (pintype "bidirectional"))
    )
    (net (code "79") (name "Net-(TINY_7-PB0)") (class "Default")
      (node (ref "R27") (pin "2") (pinfunction "2_2") (pintype "passive"))
      (node (ref "TINY_7") (pin "1") (pinfunction "PB0_1") (pintype "bidirectional"))
    )
    (net (code "80") (name "Net-(TINY_7-PB1)") (class "Default")
      (node (ref "R28") (pin "2") (pinfunction "2_2") (pintype "passive"))
      (node (ref "TINY_7") (pin "3") (pinfunction "PB1_3") (pintype "bidirectional"))
    )
    (net (code "81") (name "Net-(TINY_8-PB0)") (class "Default")
      (node (ref "R5") (pin "2") (pinfunction "2_2") (pintype "passive"))
      (node (ref "TINY_8") (pin "1") (pinfunction "PB0_1") (pintype "bidirectional"))
    )
    (net (code "82") (name "Net-(TINY_8-PB1)") (class "Default")
      (node (ref "R6") (pin "2") (pinfunction "2_2") (pintype "passive"))
      (node (ref "TINY_8") (pin "3") (pinfunction "PB1_3") (pintype "bidirectional"))
    )
    (net (code "83") (name "Net-(TINY_9-PB0)") (class "Default")
      (node (ref "R7") (pin "2") (pinfunction "2_2") (pintype "passive"))
      (node (ref "TINY_9") (pin "1") (pinfunction "PB0_1") (pintype "bidirectional"))
    )
    (net (code "84") (name "Net-(TINY_9-PB1)") (class "Default")
      (node (ref "R8") (pin "2") (pinfunction "2_2") (pintype "passive"))
      (node (ref "TINY_9") (pin "3") (pinfunction "PB1_3") (pintype "bidirectional"))
    )
    (net (code "85") (name "Net-(TINY_10-PB0)") (class "Default")
      (node (ref "R13") (pin "2") (pinfunction "2_2") (pintype "passive"))
      (node (ref "TINY_10") (pin "1") (pinfunction "PB0_1") (pintype "bidirectional"))
    )
    (net (code "86") (name "Net-(TINY_10-PB1)") (class "Default")
      (node (ref "R14") (pin "2") (pinfunction "2_2") (pintype "passive"))
      (node (ref "TINY_10") (pin "3") (pinfunction "PB1_3") (pintype "bidirectional"))
    )
    (net (code "87") (name "Net-(TINY_11-PB0)") (class "Default")
      (node (ref "R15") (pin "2") (pinfunction "2_2") (pintype "passive"))
      (node (ref "TINY_11") (pin "1") (pinfunction "PB0_1") (pintype "bidirectional"))
    )
    (net (code "88") (name "Net-(TINY_11-PB1)") (class "Default")
      (node (ref "R16") (pin "2") (pinfunction "2_2") (pintype "passive"))
      (node (ref "TINY_11") (pin "3") (pinfunction "PB1_3") (pintype "bidirectional"))
    )
    (net (code "89") (name "Net-(TINY_12-PB0)") (class "Default")
      (node (ref "R21") (pin "2") (pinfunction "2_2") (pintype "passive"))
      (node (ref "TINY_12") (pin "1") (pinfunction "PB0_1") (pintype "bidirectional"))
    )
    (net (code "90") (name "Net-(TINY_12-PB1)") (class "Default")
      (node (ref "R22") (pin "2") (pinfunction "2_2") (pintype "passive"))
      (node (ref "TINY_12") (pin "3") (pinfunction "PB1_3") (pintype "bidirectional"))
    )
    (net (code "91") (name "Net-(TINY_13-PB0)") (class "Default")
      (node (ref "R23") (pin "2") (pinfunction "2_2") (pintype "passive"))
      (node (ref "TINY_13") (pin "1") (pinfunction "PB0_1") (pintype "bidirectional"))
    )
    (net (code "92") (name "Net-(TINY_13-PB1)") (class "Default")
      (node (ref "R24") (pin "2") (pinfunction "2_2") (pintype "passive"))
      (node (ref "TINY_13") (pin "3") (pinfunction "PB1_3") (pintype "bidirectional"))
    )
    (net (code "93") (name "Net-(TINY_14-PB0)") (class "Default")
      (node (ref "R29") (pin "2") (pinfunction "2_2") (pintype "passive"))
      (node (ref "TINY_14") (pin "1") (pinfunction "PB0_1") (pintype "bidirectional"))
    )
    (net (code "94") (name "Net-(TINY_14-PB1)") (class "Default")
      (node (ref "R30") (pin "2") (pinfunction "2_2") (pintype "passive"))
      (node (ref "TINY_14") (pin "3") (pinfunction "PB1_3") (pintype "bidirectional"))
    )
    (net (code "95") (name "Net-(TINY_15-PB0)") (class "Default")
      (node (ref "R31") (pin "2") (pinfunction "2_2") (pintype "passive"))
      (node (ref "TINY_15") (pin "1") (pinfunction "PB0_1") (pintype "bidirectional"))
    )
    (net (code "96") (name "Net-(TINY_15-PB1)") (class "Default")
      (node (ref "R32") (pin "2") (pinfunction "2_2") (pintype "passive"))
      (node (ref "TINY_15") (pin "3") (pinfunction "PB1_3") (pintype "bidirectional"))
    )
    (net (code "97") (name "Net-(TP1-1)") (class "Default")
      (node (ref "TP1") (pin "P$1") (pinfunction "1_P$1") (pintype "bidirectional"))
      (node (ref "U$6") (pin "33") (pinfunction "PE2(~{HWB})_33") (pintype "bidirectional"))
    )
    (net (code "98") (name "Net-(TP3-1)") (class "Default")
      (node (ref "TP3") (pin "P$1") (pinfunction "1_P$1") (pintype "bidirectional"))
      (node (ref "U$6") (pin "1") (pinfunction "PE6(INT.6/AIN0)_1") (pintype "bidirectional"))
    )
    (net (code "99") (name "Net-(U$1-QS)") (class "Default")
      (node (ref "U$1") (pin "9") (pinfunction "QS_9") (pintype "bidirectional"))
      (node (ref "U$2") (pin "2") (pinfunction "DATA_2") (pintype "bidirectional"))
    )
    (net (code "100") (name "Net-(U$6-AREF)") (class "Default")
      (node (ref "C6") (pin "1") (pinfunction "1_1") (pintype "passive"))
      (node (ref "U$6") (pin "42") (pinfunction "AREF_42") (pintype "bidirectional"))
    )
    (net (code "101") (name "Net-(U$6-D+)") (class "Default")
      (node (ref "R34") (pin "2") (pinfunction "2_2") (pintype "passive"))
      (node (ref "U$6") (pin "4") (pinfunction "D+_4") (pintype "bidirectional"))
    )
    (net (code "102") (name "Net-(U$6-D-)") (class "Default")
      (node (ref "R33") (pin "2") (pinfunction "2_2") (pintype "passive"))
      (node (ref "U$6") (pin "3") (pinfunction "D-_3") (pintype "bidirectional"))
    )
    (net (code "103") (name "Net-(U$6-PC6(OC3A{slash}~{OC4A}))") (class "Default")
      (node (ref "R40") (pin "1") (pinfunction "1_1") (pintype "passive"))
      (node (ref "U$6") (pin "31") (pinfunction "PC6(OC3A/~{OC4A})_31") (pintype "bidirectional"))
    )
    (net (code "104") (name "Net-(U$6-PC7(ICP3{slash}CLK0{slash}OC4A))") (class "Default")
      (node (ref "R41") (pin "1") (pinfunction "1_1") (pintype "passive"))
      (node (ref "U$6") (pin "32") (pinfunction "PC7(ICP3/CLK0/OC4A)_32") (pintype "bidirectional"))
    )
    (net (code "105") (name "Net-(U$6-PF6(ADC6{slash}TDO))") (class "Default")
      (node (ref "R38") (pin "1") (pinfunction "1_1") (pintype "passive"))
      (node (ref "U$6") (pin "37") (pinfunction "PF6(ADC6/TDO)_37") (pintype "bidirectional"))
    )
    (net (code "106") (name "Net-(U$6-PF7(ADC7(TDI))") (class "Default")
      (node (ref "R39") (pin "1") (pinfunction "1_1") (pintype "passive"))
      (node (ref "U$6") (pin "36") (pinfunction "PF7(ADC7(TDI)_36") (pintype "bidirectional"))
    )
    (net (code "107") (name "Net-(U$6-UCAP)") (class "Default")
      (node (ref "C5") (pin "1") (pinfunction "1_1") (pintype "passive"))
      (node (ref "U$6") (pin "6") (pinfunction "UCAP_6") (pintype "bidirectional"))
    )
    (net (code "108") (name "Net-(U$6-XTAL1)") (class "Default")
      (node (ref "C7") (pin "1") (pinfunction "1_1") (pintype "passive"))
      (node (ref "U$6") (pin "17") (pinfunction "XTAL1_17") (pintype "bidirectional"))
      (node (ref "Y1") (pin "1") (pinfunction "1_1") (pintype "passive"))
    )
    (net (code "109") (name "Net-(U$6-XTAL2)") (class "Default")
      (node (ref "C8") (pin "1") (pinfunction "1_1") (pintype "passive"))
      (node (ref "U$6") (pin "16") (pinfunction "XTAL2_16") (pintype "bidirectional"))
      (node (ref "Y1") (pin "3") (pinfunction "2_3") (pintype "passive"))
    )
    (net (code "110") (name "Net-(U$7-D+)") (class "Default")
      (node (ref "R34") (pin "1") (pinfunction "1_1") (pintype "passive"))
      (node (ref "U$7") (pin "3") (pinfunction "D+_3") (pintype "bidirectional"))
    )
    (net (code "111") (name "Net-(U$7-D-)") (class "Default")
      (node (ref "R33") (pin "1") (pinfunction "1_1") (pintype "passive"))
      (node (ref "U$7") (pin "2") (pinfunction "D-_2") (pintype "bidirectional"))
    )
    (net (code "112") (name "unconnected-(U$1-Q'S-Pad10)") (class "Default")
      (node (ref "U$1") (pin "10") (pinfunction "Q'S_10") (pintype "bidirectional"))
    )
    (net (code "113") (name "unconnected-(U$2-Q'S-Pad10)") (class "Default")
      (node (ref "U$2") (pin "10") (pinfunction "Q'S_10") (pintype "bidirectional"))
    )
    (net (code "114") (name "unconnected-(U$2-QS-Pad9)") (class "Default")
      (node (ref "U$2") (pin "9") (pinfunction "QS_9") (pintype "bidirectional"))
    )
    (net (code "115") (name "unconnected-(U$7-ID-Pad4)") (class "Default")
      (node (ref "U$7") (pin "4") (pinfunction "ID_4") (pintype "bidirectional"))
    )
  )
)
